# rev02_23.net
KiCad netlist of a schematic drawn in Altium Designer
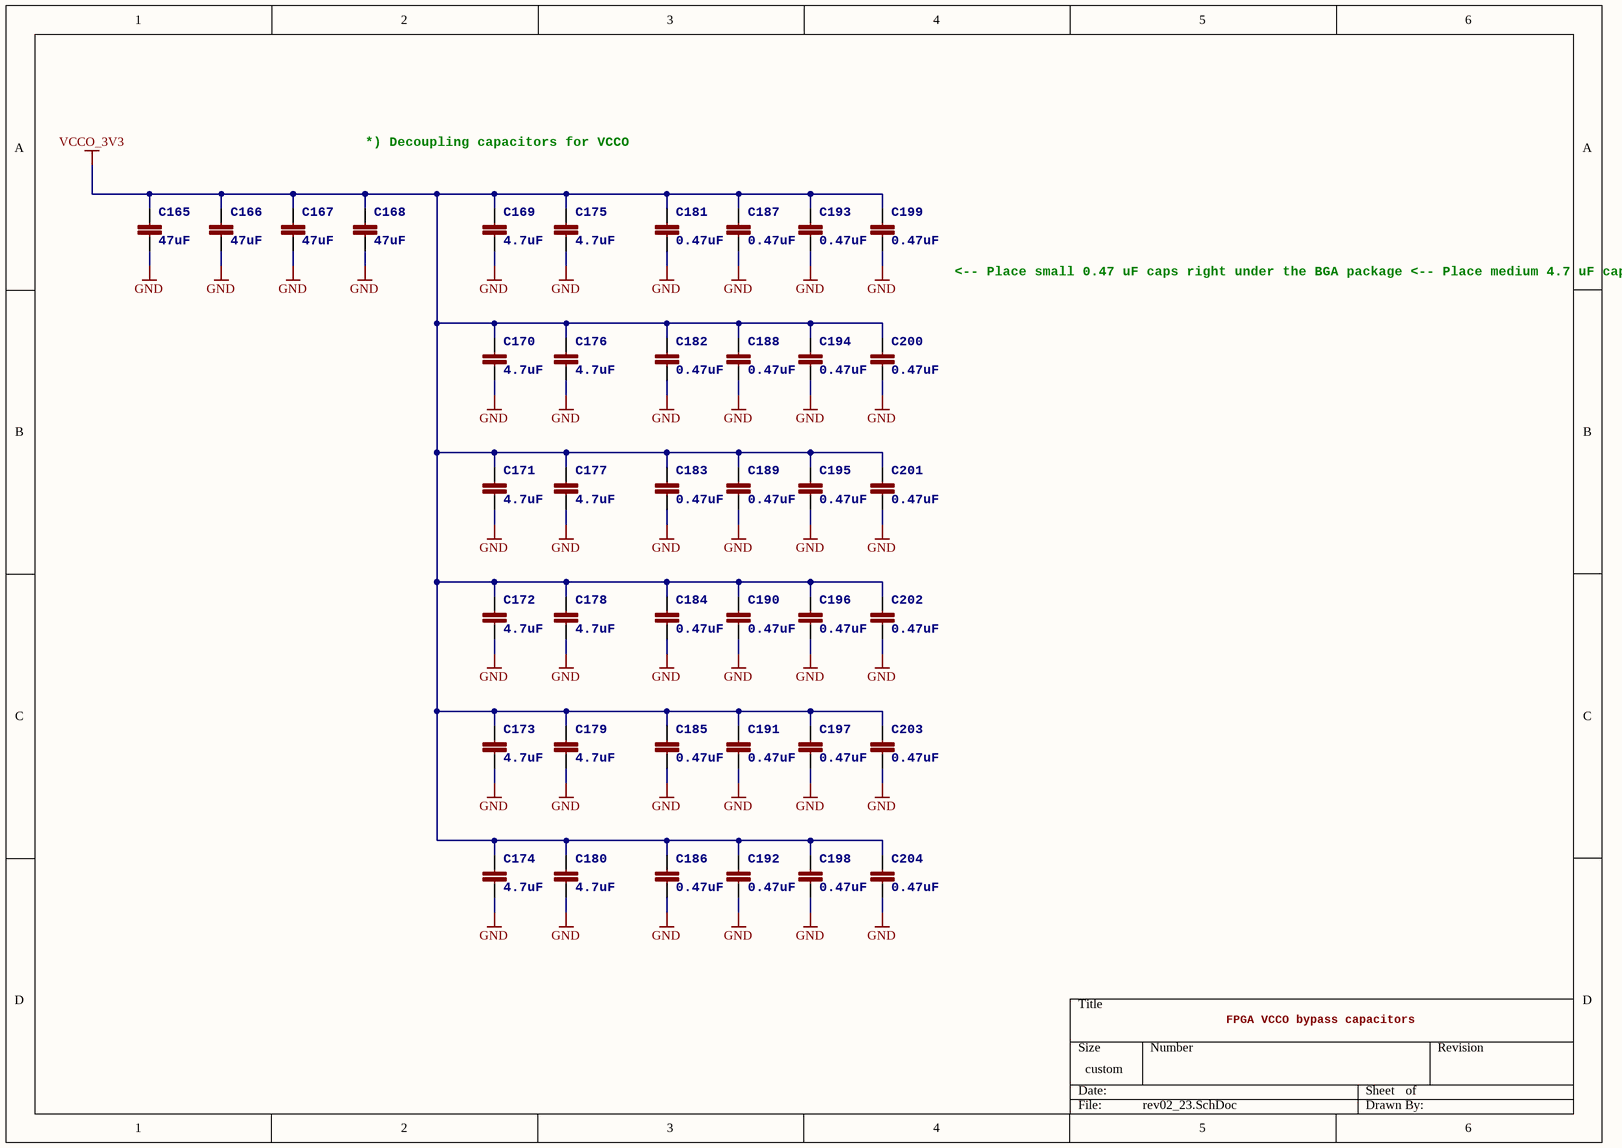
[diagram p0: rev02_23.SchDoc]

(export (version "E")
  (design (tool "Eeschema 10.0.6"))
  (components
    (comp (ref "C165")
      (value "47uF")
      (footprint "C_1210")
      (description "1210 CAPACITOR X5R 6.3V")
      (fields
        (field (name "TOLERANCE") "20%")
        (field (name ">NAME") "C165")
        (field (name "Comment") "GRM32ER70J476ME20L")
      )
      (libsource (lib "resistor") (part "C-EUC1210"))
    )
    (comp (ref "C166")
      (value "47uF")
      (footprint "C_1210")
      (description "1210 CAPACITOR X5R 6.3V")
      (fields
        (field (name "TOLERANCE") "20%")
        (field (name ">NAME") "C166")
        (field (name "Comment") "GRM32ER70J476ME20L")
      )
      (libsource (lib "resistor") (part "C-EUC1210"))
    )
    (comp (ref "C167")
      (value "47uF")
      (footprint "C_1210")
      (description "1210 CAPACITOR X5R 6.3V")
      (fields
        (field (name "TOLERANCE") "20%")
        (field (name ">NAME") "C167")
        (field (name "Comment") "GRM32ER70J476ME20L")
      )
      (libsource (lib "resistor") (part "C-EUC1210"))
    )
    (comp (ref "C168")
      (value "47uF")
      (footprint "C_1210")
      (description "1210 CAPACITOR X5R 6.3V")
      (fields
        (field (name "TOLERANCE") "20%")
        (field (name ">NAME") "C168")
        (field (name "Comment") "GRM32ER70J476ME20L")
      )
      (libsource (lib "resistor") (part "C-EUC1210"))
    )
    (comp (ref "C169")
      (value "4.7uF")
      (footprint "C_0805")
      (description "0805 CAPACITOR")
      (fields
        (field (name "TOLERANCE") "10%")
        (field (name ">NAME") "C169")
        (field (name "Comment") "GRM21BR71A475KA73L")
      )
      (libsource (lib "resistor") (part "C-EUC0603"))
    )
    (comp (ref "C170")
      (value "4.7uF")
      (footprint "C_0805")
      (description "0805 CAPACITOR")
      (fields
        (field (name "TOLERANCE") "10%")
        (field (name ">NAME") "C170")
        (field (name "Comment") "GRM21BR71A475KA73L")
      )
      (libsource (lib "resistor") (part "C-EUC0603"))
    )
    (comp (ref "C171")
      (value "4.7uF")
      (footprint "C_0805")
      (description "0805 CAPACITOR")
      (fields
        (field (name "TOLERANCE") "10%")
        (field (name ">NAME") "C171")
        (field (name "Comment") "GRM21BR71A475KA73L")
      )
      (libsource (lib "resistor") (part "C-EUC0603"))
    )
    (comp (ref "C172")
      (value "4.7uF")
      (footprint "C_0805")
      (description "0805 CAPACITOR")
      (fields
        (field (name "TOLERANCE") "10%")
        (field (name ">NAME") "C172")
        (field (name "Comment") "GRM21BR71A475KA73L")
      )
      (libsource (lib "resistor") (part "C-EUC0603"))
    )
    (comp (ref "C173")
      (value "4.7uF")
      (footprint "C_0805")
      (description "0805 CAPACITOR")
      (fields
        (field (name "TOLERANCE") "10%")
        (field (name ">NAME") "C173")
        (field (name "Comment") "GRM21BR71A475KA73L")
      )
      (libsource (lib "resistor") (part "C-EUC0603"))
    )
    (comp (ref "C174")
      (value "4.7uF")
      (footprint "C_0805")
      (description "0805 CAPACITOR")
      (fields
        (field (name "TOLERANCE") "10%")
        (field (name ">NAME") "C174")
        (field (name "Comment") "GRM21BR71A475KA73L")
      )
      (libsource (lib "resistor") (part "C-EUC0603"))
    )
    (comp (ref "C175")
      (value "4.7uF")
      (footprint "C_0805")
      (description "0805 CAPACITOR")
      (fields
        (field (name "TOLERANCE") "10%")
        (field (name ">NAME") "C175")
        (field (name "Comment") "GRM21BR71A475KA73L")
      )
      (libsource (lib "resistor") (part "C-EUC0603"))
    )
    (comp (ref "C176")
      (value "4.7uF")
      (footprint "C_0805")
      (description "0805 CAPACITOR")
      (fields
        (field (name "TOLERANCE") "10%")
        (field (name ">NAME") "C176")
        (field (name "Comment") "GRM21BR71A475KA73L")
      )
      (libsource (lib "resistor") (part "C-EUC0603"))
    )
    (comp (ref "C177")
      (value "4.7uF")
      (footprint "C_0805")
      (description "0805 CAPACITOR")
      (fields
        (field (name "TOLERANCE") "10%")
        (field (name ">NAME") "C177")
        (field (name "Comment") "GRM21BR71A475KA73L")
      )
      (libsource (lib "resistor") (part "C-EUC0603"))
    )
    (comp (ref "C178")
      (value "4.7uF")
      (footprint "C_0805")
      (description "0805 CAPACITOR")
      (fields
        (field (name "TOLERANCE") "10%")
        (field (name ">NAME") "C178")
        (field (name "Comment") "GRM21BR71A475KA73L")
      )
      (libsource (lib "resistor") (part "C-EUC0603"))
    )
    (comp (ref "C179")
      (value "4.7uF")
      (footprint "C_0805")
      (description "0805 CAPACITOR")
      (fields
        (field (name "TOLERANCE") "10%")
        (field (name ">NAME") "C179")
        (field (name "Comment") "GRM21BR71A475KA73L")
      )
      (libsource (lib "resistor") (part "C-EUC0603"))
    )
    (comp (ref "C180")
      (value "4.7uF")
      (footprint "C_0805")
      (description "0805 CAPACITOR")
      (fields
        (field (name "TOLERANCE") "10%")
        (field (name ">NAME") "C180")
        (field (name "Comment") "GRM21BR71A475KA73L")
      )
      (libsource (lib "resistor") (part "C-EUC0603"))
    )
    (comp (ref "C181")
      (value "0.47uF")
      (footprint "C_0402")
      (description "0402 CAPACITOR")
      (fields
        (field (name "TOLERANCE") "10%")
        (field (name ">NAME") "C181")
        (field (name "Comment") "GRM155R61A474KE15D")
      )
      (libsource (lib "resistor") (part "C-EUC0402"))
    )
    (comp (ref "C182")
      (value "0.47uF")
      (footprint "C_0402")
      (description "0402 CAPACITOR")
      (fields
        (field (name "TOLERANCE") "10%")
        (field (name ">NAME") "C182")
        (field (name "Comment") "GRM155R61A474KE15D")
      )
      (libsource (lib "resistor") (part "C-EUC0402"))
    )
    (comp (ref "C183")
      (value "0.47uF")
      (footprint "C_0402")
      (description "0402 CAPACITOR")
      (fields
        (field (name "TOLERANCE") "10%")
        (field (name ">NAME") "C183")
        (field (name "Comment") "GRM155R61A474KE15D")
      )
      (libsource (lib "resistor") (part "C-EUC0402"))
    )
    (comp (ref "C184")
      (value "0.47uF")
      (footprint "C_0402")
      (description "0402 CAPACITOR")
      (fields
        (field (name "TOLERANCE") "10%")
        (field (name ">NAME") "C184")
        (field (name "Comment") "GRM155R61A474KE15D")
      )
      (libsource (lib "resistor") (part "C-EUC0402"))
    )
    (comp (ref "C185")
      (value "0.47uF")
      (footprint "C_0402")
      (description "0402 CAPACITOR")
      (fields
        (field (name "TOLERANCE") "10%")
        (field (name ">NAME") "C185")
        (field (name "Comment") "GRM155R61A474KE15D")
      )
      (libsource (lib "resistor") (part "C-EUC0402"))
    )
    (comp (ref "C186")
      (value "0.47uF")
      (footprint "C_0402")
      (description "0402 CAPACITOR")
      (fields
        (field (name "TOLERANCE") "10%")
        (field (name ">NAME") "C186")
        (field (name "Comment") "GRM155R61A474KE15D")
      )
      (libsource (lib "resistor") (part "C-EUC0402"))
    )
    (comp (ref "C187")
      (value "0.47uF")
      (footprint "C_0402")
      (description "0402 CAPACITOR")
      (fields
        (field (name "TOLERANCE") "10%")
        (field (name ">NAME") "C187")
        (field (name "Comment") "GRM155R61A474KE15D")
      )
      (libsource (lib "resistor") (part "C-EUC0402"))
    )
    (comp (ref "C188")
      (value "0.47uF")
      (footprint "C_0402")
      (description "0402 CAPACITOR")
      (fields
        (field (name "TOLERANCE") "10%")
        (field (name ">NAME") "C188")
        (field (name "Comment") "GRM155R61A474KE15D")
      )
      (libsource (lib "resistor") (part "C-EUC0402"))
    )
    (comp (ref "C189")
      (value "0.47uF")
      (footprint "C_0402")
      (description "0402 CAPACITOR")
      (fields
        (field (name "TOLERANCE") "10%")
        (field (name ">NAME") "C189")
        (field (name "Comment") "GRM155R61A474KE15D")
      )
      (libsource (lib "resistor") (part "C-EUC0402"))
    )
    (comp (ref "C190")
      (value "0.47uF")
      (footprint "C_0402")
      (description "0402 CAPACITOR")
      (fields
        (field (name "TOLERANCE") "10%")
        (field (name ">NAME") "C190")
        (field (name "Comment") "GRM155R61A474KE15D")
      )
      (libsource (lib "resistor") (part "C-EUC0402"))
    )
    (comp (ref "C191")
      (value "0.47uF")
      (footprint "C_0402")
      (description "0402 CAPACITOR")
      (fields
        (field (name "TOLERANCE") "10%")
        (field (name ">NAME") "C191")
        (field (name "Comment") "GRM155R61A474KE15D")
      )
      (libsource (lib "resistor") (part "C-EUC0402"))
    )
    (comp (ref "C192")
      (value "0.47uF")
      (footprint "C_0402")
      (description "0402 CAPACITOR")
      (fields
        (field (name "TOLERANCE") "10%")
        (field (name ">NAME") "C192")
        (field (name "Comment") "GRM155R61A474KE15D")
      )
      (libsource (lib "resistor") (part "C-EUC0402"))
    )
    (comp (ref "C193")
      (value "0.47uF")
      (footprint "C_0402")
      (description "0402 CAPACITOR")
      (fields
        (field (name "TOLERANCE") "10%")
        (field (name ">NAME") "C193")
        (field (name "Comment") "GRM155R61A474KE15D")
      )
      (libsource (lib "resistor") (part "C-EUC0402"))
    )
    (comp (ref "C194")
      (value "0.47uF")
      (footprint "C_0402")
      (description "0402 CAPACITOR")
      (fields
        (field (name "TOLERANCE") "10%")
        (field (name ">NAME") "C194")
        (field (name "Comment") "GRM155R61A474KE15D")
      )
      (libsource (lib "resistor") (part "C-EUC0402"))
    )
    (comp (ref "C195")
      (value "0.47uF")
      (footprint "C_0402")
      (description "0402 CAPACITOR")
      (fields
        (field (name "TOLERANCE") "10%")
        (field (name ">NAME") "C195")
        (field (name "Comment") "GRM155R61A474KE15D")
      )
      (libsource (lib "resistor") (part "C-EUC0402"))
    )
    (comp (ref "C196")
      (value "0.47uF")
      (footprint "C_0402")
      (description "0402 CAPACITOR")
      (fields
        (field (name "TOLERANCE") "10%")
        (field (name ">NAME") "C196")
        (field (name "Comment") "GRM155R61A474KE15D")
      )
      (libsource (lib "resistor") (part "C-EUC0402"))
    )
    (comp (ref "C197")
      (value "0.47uF")
      (footprint "C_0402")
      (description "0402 CAPACITOR")
      (fields
        (field (name "TOLERANCE") "10%")
        (field (name ">NAME") "C197")
        (field (name "Comment") "GRM155R61A474KE15D")
      )
      (libsource (lib "resistor") (part "C-EUC0402"))
    )
    (comp (ref "C198")
      (value "0.47uF")
      (footprint "C_0402")
      (description "0402 CAPACITOR")
      (fields
        (field (name "TOLERANCE") "10%")
        (field (name ">NAME") "C198")
        (field (name "Comment") "GRM155R61A474KE15D")
      )
      (libsource (lib "resistor") (part "C-EUC0402"))
    )
    (comp (ref "C199")
      (value "0.47uF")
      (footprint "C_0402")
      (description "0402 CAPACITOR")
      (fields
        (field (name "TOLERANCE") "10%")
        (field (name ">NAME") "C199")
        (field (name "Comment") "GRM155R61A474KE15D")
      )
      (libsource (lib "resistor") (part "C-EUC0402"))
    )
    (comp (ref "C200")
      (value "0.47uF")
      (footprint "C_0402")
      (description "0402 CAPACITOR")
      (fields
        (field (name "TOLERANCE") "10%")
        (field (name ">NAME") "C200")
        (field (name "Comment") "GRM155R61A474KE15D")
      )
      (libsource (lib "resistor") (part "C-EUC0402"))
    )
    (comp (ref "C201")
      (value "0.47uF")
      (footprint "C_0402")
      (description "0402 CAPACITOR")
      (fields
        (field (name "TOLERANCE") "10%")
        (field (name ">NAME") "C201")
        (field (name "Comment") "GRM155R61A474KE15D")
      )
      (libsource (lib "resistor") (part "C-EUC0402"))
    )
    (comp (ref "C202")
      (value "0.47uF")
      (footprint "C_0402")
      (description "0402 CAPACITOR")
      (fields
        (field (name "TOLERANCE") "10%")
        (field (name ">NAME") "C202")
        (field (name "Comment") "GRM155R61A474KE15D")
      )
      (libsource (lib "resistor") (part "C-EUC0402"))
    )
    (comp (ref "C203")
      (value "0.47uF")
      (footprint "C_0402")
      (description "0402 CAPACITOR")
      (fields
        (field (name "TOLERANCE") "10%")
        (field (name ">NAME") "C203")
        (field (name "Comment") "GRM155R61A474KE15D")
      )
      (libsource (lib "resistor") (part "C-EUC0402"))
    )
    (comp (ref "C204")
      (value "0.47uF")
      (footprint "C_0402")
      (description "0402 CAPACITOR")
      (fields
        (field (name "TOLERANCE") "10%")
        (field (name ">NAME") "C204")
        (field (name "Comment") "GRM155R61A474KE15D")
      )
      (libsource (lib "resistor") (part "C-EUC0402"))
    )
  )
  (nets
    (net (code "1") (name "GND") (class "Default")
      (node (ref "C165") (pin "2") (pinfunction "2_2") (pintype "passive"))
      (node (ref "C166") (pin "2") (pinfunction "2_2") (pintype "passive"))
      (node (ref "C167") (pin "2") (pinfunction "2_2") (pintype "passive"))
      (node (ref "C168") (pin "2") (pinfunction "2_2") (pintype "passive"))
      (node (ref "C169") (pin "2") (pinfunction "2_2") (pintype "passive"))
      (node (ref "C170") (pin "2") (pinfunction "2_2") (pintype "passive"))
      (node (ref "C171") (pin "2") (pinfunction "2_2") (pintype "passive"))
      (node (ref "C172") (pin "2") (pinfunction "2_2") (pintype "passive"))
      (node (ref "C173") (pin "2") (pinfunction "2_2") (pintype "passive"))
      (node (ref "C174") (pin "2") (pinfunction "2_2") (pintype "passive"))
      (node (ref "C175") (pin "2") (pinfunction "2_2") (pintype "passive"))
      (node (ref "C176") (pin "2") (pinfunction "2_2") (pintype "passive"))
      (node (ref "C177") (pin "2") (pinfunction "2_2") (pintype "passive"))
      (node (ref "C178") (pin "2") (pinfunction "2_2") (pintype "passive"))
      (node (ref "C179") (pin "2") (pinfunction "2_2") (pintype "passive"))
      (node (ref "C180") (pin "2") (pinfunction "2_2") (pintype "passive"))
      (node (ref "C181") (pin "2") (pinfunction "2_2") (pintype "passive"))
      (node (ref "C182") (pin "2") (pinfunction "2_2") (pintype "passive"))
      (node (ref "C183") (pin "2") (pinfunction "2_2") (pintype "passive"))
      (node (ref "C184") (pin "2") (pinfunction "2_2") (pintype "passive"))
      (node (ref "C185") (pin "2") (pinfunction "2_2") (pintype "passive"))
      (node (ref "C186") (pin "2") (pinfunction "2_2") (pintype "passive"))
      (node (ref "C187") (pin "2") (pinfunction "2_2") (pintype "passive"))
      (node (ref "C188") (pin "2") (pinfunction "2_2") (pintype "passive"))
      (node (ref "C189") (pin "2") (pinfunction "2_2") (pintype "passive"))
      (node (ref "C190") (pin "2") (pinfunction "2_2") (pintype "passive"))
      (node (ref "C191") (pin "2") (pinfunction "2_2") (pintype "passive"))
      (node (ref "C192") (pin "2") (pinfunction "2_2") (pintype "passive"))
      (node (ref "C193") (pin "2") (pinfunction "2_2") (pintype "passive"))
      (node (ref "C194") (pin "2") (pinfunction "2_2") (pintype "passive"))
      (node (ref "C195") (pin "2") (pinfunction "2_2") (pintype "passive"))
      (node (ref "C196") (pin "2") (pinfunction "2_2") (pintype "passive"))
      (node (ref "C197") (pin "2") (pinfunction "2_2") (pintype "passive"))
      (node (ref "C198") (pin "2") (pinfunction "2_2") (pintype "passive"))
      (node (ref "C199") (pin "2") (pinfunction "2_2") (pintype "passive"))
      (node (ref "C200") (pin "2") (pinfunction "2_2") (pintype "passive"))
      (node (ref "C201") (pin "2") (pinfunction "2_2") (pintype "passive"))
      (node (ref "C202") (pin "2") (pinfunction "2_2") (pintype "passive"))
      (node (ref "C203") (pin "2") (pinfunction "2_2") (pintype "passive"))
      (node (ref "C204") (pin "2") (pinfunction "2_2") (pintype "passive"))
    )
    (net (code "2") (name "VCCO_3V3") (class "Default")
      (node (ref "C165") (pin "1") (pinfunction "1_1") (pintype "passive"))
      (node (ref "C166") (pin "1") (pinfunction "1_1") (pintype "passive"))
      (node (ref "C167") (pin "1") (pinfunction "1_1") (pintype "passive"))
      (node (ref "C168") (pin "1") (pinfunction "1_1") (pintype "passive"))
      (node (ref "C169") (pin "1") (pinfunction "1_1") (pintype "passive"))
      (node (ref "C170") (pin "1") (pinfunction "1_1") (pintype "passive"))
      (node (ref "C171") (pin "1") (pinfunction "1_1") (pintype "passive"))
      (node (ref "C172") (pin "1") (pinfunction "1_1") (pintype "passive"))
      (node (ref "C173") (pin "1") (pinfunction "1_1") (pintype "passive"))
      (node (ref "C174") (pin "1") (pinfunction "1_1") (pintype "passive"))
      (node (ref "C175") (pin "1") (pinfunction "1_1") (pintype "passive"))
      (node (ref "C176") (pin "1") (pinfunction "1_1") (pintype "passive"))
      (node (ref "C177") (pin "1") (pinfunction "1_1") (pintype "passive"))
      (node (ref "C178") (pin "1") (pinfunction "1_1") (pintype "passive"))
      (node (ref "C179") (pin "1") (pinfunction "1_1") (pintype "passive"))
      (node (ref "C180") (pin "1") (pinfunction "1_1") (pintype "passive"))
      (node (ref "C181") (pin "1") (pinfunction "1_1") (pintype "passive"))
      (node (ref "C182") (pin "1") (pinfunction "1_1") (pintype "passive"))
      (node (ref "C183") (pin "1") (pinfunction "1_1") (pintype "passive"))
      (node (ref "C184") (pin "1") (pinfunction "1_1") (pintype "passive"))
      (node (ref "C185") (pin "1") (pinfunction "1_1") (pintype "passive"))
      (node (ref "C186") (pin "1") (pinfunction "1_1") (pintype "passive"))
      (node (ref "C187") (pin "1") (pinfunction "1_1") (pintype "passive"))
      (node (ref "C188") (pin "1") (pinfunction "1_1") (pintype "passive"))
      (node (ref "C189") (pin "1") (pinfunction "1_1") (pintype "passive"))
      (node (ref "C190") (pin "1") (pinfunction "1_1") (pintype "passive"))
      (node (ref "C191") (pin "1") (pinfunction "1_1") (pintype "passive"))
      (node (ref "C192") (pin "1") (pinfunction "1_1") (pintype "passive"))
      (node (ref "C193") (pin "1") (pinfunction "1_1") (pintype "passive"))
      (node (ref "C194") (pin "1") (pinfunction "1_1") (pintype "passive"))
      (node (ref "C195") (pin "1") (pinfunction "1_1") (pintype "passive"))
      (node (ref "C196") (pin "1") (pinfunction "1_1") (pintype "passive"))
      (node (ref "C197") (pin "1") (pinfunction "1_1") (pintype "passive"))
      (node (ref "C198") (pin "1") (pinfunction "1_1") (pintype "passive"))
      (node (ref "C199") (pin "1") (pinfunction "1_1") (pintype "passive"))
      (node (ref "C200") (pin "1") (pinfunction "1_1") (pintype "passive"))
      (node (ref "C201") (pin "1") (pinfunction "1_1") (pintype "passive"))
      (node (ref "C202") (pin "1") (pinfunction "1_1") (pintype "passive"))
      (node (ref "C203") (pin "1") (pinfunction "1_1") (pintype "passive"))
      (node (ref "C204") (pin "1") (pinfunction "1_1") (pintype "passive"))
    )
  )
)
